# STM32.net
KiCad netlist of a schematic drawn in Altium Designer
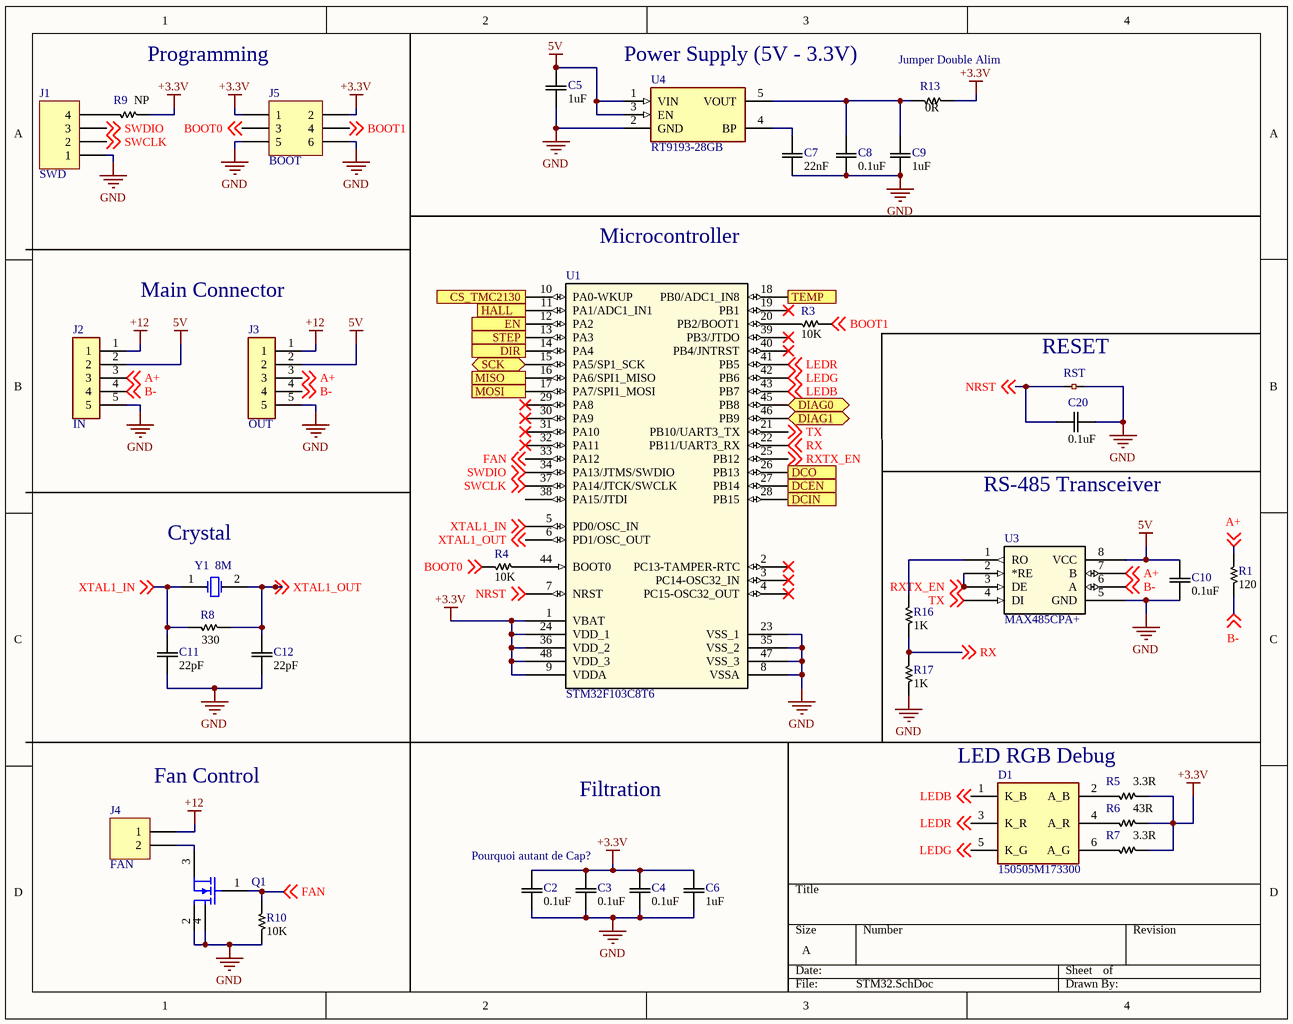
[diagram p0: STM32.SchDoc]

(export (version "E")
  (design (tool "Eeschema 10.0.6"))
  (components
    (comp (ref "C2")
      (value "0.1uF")
      (footprint "0603")
      (description "Capacitor SMD 1206")
      (fields
        (field (name "MANUFACTURER_PART_NUMBER") "12065A820JAT2A")
        (field (name "Comment") "Capacitor 1206")
        (field (name "COPYRIGHT") "Copyright (C) 2018 Accelerated Designs. All rights reserved")
      )
      (libsource (lib "Schematic_Emile") (part "Capacitor 1206"))
    )
    (comp (ref "C3")
      (value "0.1uF")
      (footprint "0603")
      (description "Capacitor SMD 1206")
      (fields
        (field (name "MANUFACTURER_PART_NUMBER") "12065A820JAT2A")
        (field (name "Comment") "Capacitor 1206")
        (field (name "COPYRIGHT") "Copyright (C) 2018 Accelerated Designs. All rights reserved")
      )
      (libsource (lib "Schematic_Emile") (part "Capacitor 1206"))
    )
    (comp (ref "C4")
      (value "0.1uF")
      (footprint "0603")
      (description "Capacitor SMD 1206")
      (fields
        (field (name "MANUFACTURER_PART_NUMBER") "12065A820JAT2A")
        (field (name "Comment") "Capacitor 1206")
        (field (name "COPYRIGHT") "Copyright (C) 2018 Accelerated Designs. All rights reserved")
      )
      (libsource (lib "Schematic_Emile") (part "Capacitor 1206"))
    )
    (comp (ref "C5")
      (value "1uF")
      (footprint "0603")
      (description "Capacitor SMD 1206")
      (fields
        (field (name "MANUFACTURER_PART_NUMBER") "12065A820JAT2A")
        (field (name "Comment") "Capacitor 1206")
        (field (name "COPYRIGHT") "Copyright (C) 2018 Accelerated Designs. All rights reserved")
      )
      (libsource (lib "Schematic_Emile") (part "Capacitor 1206"))
    )
    (comp (ref "C6")
      (value "1uF")
      (footprint "0603")
      (description "Capacitor SMD 1206")
      (fields
        (field (name "MANUFACTURER_PART_NUMBER") "12065A820JAT2A")
        (field (name "Comment") "Capacitor 1206")
        (field (name "COPYRIGHT") "Copyright (C) 2018 Accelerated Designs. All rights reserved")
      )
      (libsource (lib "Schematic_Emile") (part "Capacitor 1206"))
    )
    (comp (ref "C7")
      (value "22nF")
      (footprint "0603")
      (description "Capacitor SMD 1206")
      (fields
        (field (name "MANUFACTURER_PART_NUMBER") "12065A820JAT2A")
        (field (name "Comment") "Capacitor 1206")
        (field (name "COPYRIGHT") "Copyright (C) 2018 Accelerated Designs. All rights reserved")
      )
      (libsource (lib "Schematic_Emile") (part "Capacitor 1206"))
    )
    (comp (ref "C8")
      (value "0.1uF")
      (footprint "0603")
      (description "Capacitor SMD 1206")
      (fields
        (field (name "MANUFACTURER_PART_NUMBER") "12065A820JAT2A")
        (field (name "Comment") "Capacitor 1206")
        (field (name "COPYRIGHT") "Copyright (C) 2018 Accelerated Designs. All rights reserved")
      )
      (libsource (lib "Schematic_Emile") (part "Capacitor 1206"))
    )
    (comp (ref "C9")
      (value "1uF")
      (footprint "0603")
      (description "Capacitor SMD 1206")
      (fields
        (field (name "MANUFACTURER_PART_NUMBER") "12065A820JAT2A")
        (field (name "Comment") "Capacitor 1206")
        (field (name "COPYRIGHT") "Copyright (C) 2018 Accelerated Designs. All rights reserved")
      )
      (libsource (lib "Schematic_Emile") (part "Capacitor 1206"))
    )
    (comp (ref "C10")
      (value "0.1uF")
      (footprint "0603")
      (description "Capacitor SMD 1206")
      (fields
        (field (name "MANUFACTURER_PART_NUMBER") "12065A820JAT2A")
        (field (name "Comment") "Capacitor 1206")
        (field (name "COPYRIGHT") "Copyright (C) 2018 Accelerated Designs. All rights reserved")
      )
      (libsource (lib "Schematic_Emile") (part "Capacitor 1206"))
    )
    (comp (ref "C11")
      (value "22pF")
      (footprint "0603")
      (description "Capacitor SMD 1206")
      (fields
        (field (name "MANUFACTURER_PART_NUMBER") "12065A820JAT2A")
        (field (name "Comment") "Capacitor 1206")
        (field (name "COPYRIGHT") "Copyright (C) 2018 Accelerated Designs. All rights reserved")
      )
      (libsource (lib "Schematic_Emile") (part "Capacitor 1206"))
    )
    (comp (ref "C12")
      (value "22pF")
      (footprint "0603")
      (description "Capacitor SMD 1206")
      (fields
        (field (name "MANUFACTURER_PART_NUMBER") "12065A820JAT2A")
        (field (name "Comment") "Capacitor 1206")
        (field (name "COPYRIGHT") "Copyright (C) 2018 Accelerated Designs. All rights reserved")
      )
      (libsource (lib "Schematic_Emile") (part "Capacitor 1206"))
    )
    (comp (ref "C20")
      (value "0.1uF")
      (footprint "0603")
      (description "Capacitor SMD 1206")
      (fields
        (field (name "MANUFACTURER_PART_NUMBER") "12065A820JAT2A")
        (field (name "Comment") "Capacitor 1206")
        (field (name "COPYRIGHT") "Copyright (C) 2018 Accelerated Designs. All rights reserved")
      )
      (libsource (lib "Schematic_Emile") (part "Capacitor 1206"))
    )
    (comp (ref "D1")
      (value "150505M173300")
      (footprint "LED 5050")
      (description "LED")
      (fields
        (field (name "MOUSER PART NUMBER") "710-150505M173300")
        (field (name "RS PART NUMBER") "1766248P")
      )
      (libsource (lib "Schematic_Emile") (part "150505M173300"))
    )
    (comp (ref "J1")
      (value "SWD")
      (footprint "HDR1X4")
      (description "Header, 4-Pin")
      (fields (field (name "PUBLISHER") "Altium Limited"))
      (libsource (lib "Miscellaneous Connectors") (part "Header 4"))
    )
    (comp (ref "J2")
      (value "IN")
      (footprint "JST 5POS 2.5mm 90°")
      (description "Connector")
      (fields (field (name "MANUFACTURER_PART_NUMBER") "S5B-XH-A-1(LF)(SN)"))
      (libsource (lib "Schematic_Emile") (part "JST 5POS"))
    )
    (comp (ref "J3")
      (value "OUT")
      (footprint "JST 5POS 2.5mm 90°")
      (description "Connector")
      (fields (field (name "MANUFACTURER_PART_NUMBER") "S5B-XH-A-1(LF)(SN)"))
      (libsource (lib "Schematic_Emile") (part "JST 5POS"))
    )
    (comp (ref "J4")
      (value "FAN")
      (footprint "HDR1X2")
      (description "Header, 2-Pin")
      (fields (field (name "PUBLISHER") "Altium Limited"))
      (libsource (lib "Miscellaneous Connectors") (part "Header 2"))
    )
    (comp (ref "J5")
      (value "BOOT")
      (footprint "Header 3x2 1.27mm SMD")
      (description "Header, 3-Pin, Dual row")
      (fields (field (name "PUBLISHER") "Altium Limited"))
      (libsource (lib "Miscellaneous Connectors") (part "Header 3X2"))
    )
    (comp (ref "Q1")
      (value "MOSFET N-CH")
      (footprint "SOT223_M")
      (description "55V 7A SOT223")
      (libsource (lib "Schematic_Emile") (part "MOSFET N-CH"))
    )
    (comp (ref "R1")
      (value "120")
      (footprint "0603")
      (description "Resistor 0603 SMD")
      (fields
        (field (name "MANUFACTURER_PART_NUMBER") "ERJ8CWFR024V")
        (field (name "Comment") "Resistor 0603")
        (field (name "COPYRIGHT") "Copyright (C) 2018 Accelerated Designs. All rights reserved")
      )
      (libsource (lib "Schematic_Emile") (part "Resistor 1206"))
    )
    (comp (ref "R3")
      (value "10K")
      (footprint "0603")
      (description "Resistor 1206 SMD")
      (fields
        (field (name "MANUFACTURER_PART_NUMBER") "ERJ8CWFR024V")
        (field (name "Comment") "Resistor 1206")
        (field (name "COPYRIGHT") "Copyright (C) 2018 Accelerated Designs. All rights reserved")
      )
      (libsource (lib "Schematic_Emile") (part "Resistor 1206"))
    )
    (comp (ref "R4")
      (value "10K")
      (footprint "0603")
      (description "Resistor 1206 SMD")
      (fields
        (field (name "MANUFACTURER_PART_NUMBER") "ERJ8CWFR024V")
        (field (name "Comment") "Resistor 1206")
        (field (name "COPYRIGHT") "Copyright (C) 2018 Accelerated Designs. All rights reserved")
      )
      (libsource (lib "Schematic_Emile") (part "Resistor 1206"))
    )
    (comp (ref "R5")
      (value "3.3R")
      (footprint "0603")
      (description "Resistor 0603 SMD")
      (fields
        (field (name "MANUFACTURER_PART_NUMBER") "ERJ8CWFR024V")
        (field (name "Comment") "Resistor 0603")
        (field (name "COPYRIGHT") "Copyright (C) 2018 Accelerated Designs. All rights reserved")
      )
      (libsource (lib "Schematic_Emile") (part "Resistor 1206"))
    )
    (comp (ref "R6")
      (value "43R")
      (footprint "0603")
      (description "Resistor 0603 SMD")
      (fields
        (field (name "MANUFACTURER_PART_NUMBER") "ERJ8CWFR024V")
        (field (name "Comment") "Resistor 0603")
        (field (name "COPYRIGHT") "Copyright (C) 2018 Accelerated Designs. All rights reserved")
      )
      (libsource (lib "Schematic_Emile") (part "Resistor 1206"))
    )
    (comp (ref "R7")
      (value "3.3R")
      (footprint "0603")
      (description "Resistor 0603 SMD")
      (fields
        (field (name "MANUFACTURER_PART_NUMBER") "ERJ8CWFR024V")
        (field (name "Comment") "Resistor 0603")
        (field (name "COPYRIGHT") "Copyright (C) 2018 Accelerated Designs. All rights reserved")
      )
      (libsource (lib "Schematic_Emile") (part "Resistor 1206"))
    )
    (comp (ref "R8")
      (value "330")
      (footprint "0603")
      (description "Resistor 0603 SMD")
      (fields
        (field (name "MANUFACTURER_PART_NUMBER") "ERJ8CWFR024V")
        (field (name "Comment") "Resistor 0603")
        (field (name "COPYRIGHT") "Copyright (C) 2018 Accelerated Designs. All rights reserved")
      )
      (libsource (lib "Schematic_Emile") (part "Resistor 1206"))
    )
    (comp (ref "R9")
      (value "NP")
      (footprint "0603")
      (description "Resistor 1206 SMD")
      (fields
        (field (name "MANUFACTURER_PART_NUMBER") "ERJ8CWFR024V")
        (field (name "Comment") "Jumper 0603")
        (field (name "COPYRIGHT") "Copyright (C) 2018 Accelerated Designs. All rights reserved")
      )
      (libsource (lib "Schematic_Emile") (part "Resistor 1206"))
    )
    (comp (ref "R10")
      (value "10K")
      (footprint "0603")
      (description "Resistor 0603 SMD")
      (fields
        (field (name "MANUFACTURER_PART_NUMBER") "ERJ8CWFR024V")
        (field (name "Comment") "Resistor 0603")
        (field (name "COPYRIGHT") "Copyright (C) 2018 Accelerated Designs. All rights reserved")
      )
      (libsource (lib "Schematic_Emile") (part "Resistor 1206"))
    )
    (comp (ref "R13")
      (value "0R")
      (footprint "0603")
      (description "Resistor 1206 SMD")
      (fields
        (field (name "MANUFACTURER_PART_NUMBER") "ERJ8CWFR024V")
        (field (name "Comment") "Jumper 0603")
        (field (name "COPYRIGHT") "Copyright (C) 2018 Accelerated Designs. All rights reserved")
      )
      (libsource (lib "Schematic_Emile") (part "Resistor 1206"))
    )
    (comp (ref "R16")
      (value "1K")
      (footprint "0603")
      (description "Resistor 0603 SMD")
      (fields
        (field (name "MANUFACTURER_PART_NUMBER") "ERJ8CWFR024V")
        (field (name "Comment") "Resistor 0603")
        (field (name "COPYRIGHT") "Copyright (C) 2018 Accelerated Designs. All rights reserved")
      )
      (libsource (lib "Schematic_Emile") (part "Resistor 1206"))
    )
    (comp (ref "R17")
      (value "1K")
      (footprint "0603")
      (description "Resistor 0603 SMD")
      (fields
        (field (name "MANUFACTURER_PART_NUMBER") "ERJ8CWFR024V")
        (field (name "Comment") "Resistor 0603")
        (field (name "COPYRIGHT") "Copyright (C) 2018 Accelerated Designs. All rights reserved")
      )
      (libsource (lib "Schematic_Emile") (part "Resistor 1206"))
    )
    (comp (ref "RST")
      (value "PAD")
      (footprint "PAD")
      (description "SMD Pad for contact")
      (libsource (lib "Schematic_Emile") (part "PAD"))
    )
    (comp (ref "U1")
      (value "STM32F103C8T6")
      (footprint "LQFP-48")
      (description "Integrated Circuit STM32")
      (fields (field (name "COPYRIGHT") "Copyright (C) 2018 Accelerated Designs. All rights reserved"))
      (libsource (lib "Schematic_Emile") (part "STM32F103C8T6"))
    )
    (comp (ref "U3")
      (value "MAX485CPA+")
      (footprint "DIP 8 - 3D")
      (description "RS485 Communication")
      (fields (field (name "COPYRIGHT") "Copyright (C) 2018 Accelerated Designs. All rights reserved"))
      (libsource (lib "Schematic_Emile") (part "MAX485CPA+"))
    )
    (comp (ref "U4")
      (value "RT9193-28GB")
      (footprint "SamacSys:SOT94P279X130-5N")
      (description "Voltage Regulator 3.3V")
      (libsource (lib "Schematic_Emile") (part "RT9193-28GB"))
    )
    (comp (ref "Y1")
      (value "8M")
      (footprint "ATS080B-E")
      (description "Crystal Oscillator")
      (fields (field (name "PUBLISHER") "Altium Limited"))
      (libsource (lib "Miscellaneous Devices") (part "XTAL"))
    )
  )
  (nets
    (net (code "1") (name "+3.3V") (class "Default")
      (node (ref "C2") (pin "2") (pinfunction "2_2") (pintype "passive"))
      (node (ref "C3") (pin "2") (pinfunction "2_2") (pintype "passive"))
      (node (ref "C4") (pin "2") (pinfunction "2_2") (pintype "passive"))
      (node (ref "C6") (pin "2") (pinfunction "2_2") (pintype "passive"))
      (node (ref "J5") (pin "1") (pinfunction "1_1") (pintype "passive"))
      (node (ref "J5") (pin "2") (pinfunction "2_2") (pintype "passive"))
      (node (ref "R13") (pin "2") (pinfunction "2_2") (pintype "passive"))
      (node (ref "R5") (pin "2") (pinfunction "2_2") (pintype "passive"))
      (node (ref "R6") (pin "2") (pinfunction "2_2") (pintype "passive"))
      (node (ref "R7") (pin "2") (pinfunction "2_2") (pintype "passive"))
      (node (ref "R9") (pin "2") (pinfunction "2_2") (pintype "passive"))
      (node (ref "U1") (pin "1") (pinfunction "VBAT_1") (pintype "power_in"))
      (node (ref "U1") (pin "24") (pinfunction "VDD_1_24") (pintype "power_in"))
      (node (ref "U1") (pin "36") (pinfunction "VDD_2_36") (pintype "power_in"))
      (node (ref "U1") (pin "48") (pinfunction "VDD_3_48") (pintype "power_in"))
      (node (ref "U1") (pin "9") (pinfunction "VDDA_9") (pintype "power_in"))
    )
    (net (code "2") (name "+12") (class "Default")
      (node (ref "J2") (pin "1") (pinfunction "1_1") (pintype "passive"))
      (node (ref "J3") (pin "1") (pinfunction "1_1") (pintype "passive"))
      (node (ref "J4") (pin "1") (pinfunction "1_1") (pintype "passive"))
    )
    (net (code "3") (name "/CS_TMC2130") (class "Default")
      (node (ref "U1") (pin "10") (pinfunction "PA0-WKUP_10") (pintype "bidirectional"))
    )
    (net (code "4") (name "/DCEN") (class "Default")
      (node (ref "U1") (pin "27") (pinfunction "PB14_27") (pintype "bidirectional"))
    )
    (net (code "5") (name "/DCIN") (class "Default")
      (node (ref "U1") (pin "28") (pinfunction "PB15_28") (pintype "bidirectional"))
    )
    (net (code "6") (name "/DCO") (class "Default")
      (node (ref "U1") (pin "26") (pinfunction "PB13_26") (pintype "bidirectional"))
    )
    (net (code "7") (name "/DIAG0") (class "Default")
      (node (ref "U1") (pin "45") (pinfunction "PB8_45") (pintype "bidirectional"))
    )
    (net (code "8") (name "/DIAG1") (class "Default")
      (node (ref "U1") (pin "46") (pinfunction "PB9_46") (pintype "bidirectional"))
    )
    (net (code "9") (name "/DIR") (class "Default")
      (node (ref "U1") (pin "14") (pinfunction "PA4_14") (pintype "bidirectional"))
    )
    (net (code "10") (name "/EN") (class "Default")
      (node (ref "U1") (pin "12") (pinfunction "PA2_12") (pintype "bidirectional"))
    )
    (net (code "11") (name "/HALL") (class "Default")
      (node (ref "U1") (pin "11") (pinfunction "PA1/ADC1_IN1_11") (pintype "bidirectional"))
    )
    (net (code "12") (name "/MISO") (class "Default")
      (node (ref "U1") (pin "16") (pinfunction "PA6/SPI1_MISO_16") (pintype "bidirectional"))
    )
    (net (code "13") (name "/MOSI") (class "Default")
      (node (ref "U1") (pin "17") (pinfunction "PA7/SPI1_MOSI_17") (pintype "bidirectional"))
    )
    (net (code "14") (name "/SCK") (class "Default")
      (node (ref "U1") (pin "15") (pinfunction "PA5/SP1_SCK_15") (pintype "bidirectional"))
    )
    (net (code "15") (name "/STEP") (class "Default")
      (node (ref "U1") (pin "13") (pinfunction "PA3_13") (pintype "bidirectional"))
    )
    (net (code "16") (name "/TEMP") (class "Default")
      (node (ref "U1") (pin "18") (pinfunction "PB0/ADC1_IN8_18") (pintype "bidirectional"))
    )
    (net (code "17") (name "5V") (class "Default")
      (node (ref "C10") (pin "2") (pinfunction "2_2") (pintype "passive"))
      (node (ref "C5") (pin "2") (pinfunction "2_2") (pintype "passive"))
      (node (ref "J2") (pin "2") (pinfunction "2_2") (pintype "passive"))
      (node (ref "J3") (pin "2") (pinfunction "2_2") (pintype "passive"))
      (node (ref "U3") (pin "8") (pinfunction "VCC_8") (pintype "power_in"))
      (node (ref "U4") (pin "1") (pinfunction "VIN_1") (pintype "input"))
      (node (ref "U4") (pin "3") (pinfunction "EN_3") (pintype "input"))
    )
    (net (code "18") (name "A+") (class "Default")
      (node (ref "J2") (pin "3") (pinfunction "3_3") (pintype "passive"))
      (node (ref "J3") (pin "3") (pinfunction "3_3") (pintype "passive"))
      (node (ref "R1") (pin "2") (pinfunction "2_2") (pintype "passive"))
      (node (ref "U3") (pin "7") (pinfunction "B_7") (pintype "bidirectional"))
    )
    (net (code "19") (name "B-") (class "Default")
      (node (ref "J2") (pin "4") (pinfunction "4_4") (pintype "passive"))
      (node (ref "J3") (pin "4") (pinfunction "4_4") (pintype "passive"))
      (node (ref "R1") (pin "1") (pinfunction "1_1") (pintype "passive"))
      (node (ref "U3") (pin "6") (pinfunction "A_6") (pintype "bidirectional"))
    )
    (net (code "20") (name "BOOT0") (class "Default")
      (node (ref "J5") (pin "3") (pinfunction "3_3") (pintype "passive"))
      (node (ref "R4") (pin "1") (pinfunction "1_1") (pintype "passive"))
    )
    (net (code "21") (name "BOOT1") (class "Default")
      (node (ref "J5") (pin "4") (pinfunction "4_4") (pintype "passive"))
      (node (ref "R3") (pin "2") (pinfunction "2_2") (pintype "passive"))
    )
    (net (code "22") (name "FAN") (class "Default")
      (node (ref "Q1") (pin "1") (pinfunction "G_1") (pintype "passive"))
      (node (ref "R10") (pin "2") (pinfunction "2_2") (pintype "passive"))
      (node (ref "U1") (pin "33") (pinfunction "PA12_33") (pintype "bidirectional"))
    )
    (net (code "23") (name "GND") (class "Default")
      (node (ref "C10") (pin "1") (pinfunction "1_1") (pintype "passive"))
      (node (ref "C11") (pin "1") (pinfunction "1_1") (pintype "passive"))
      (node (ref "C12") (pin "1") (pinfunction "1_1") (pintype "passive"))
      (node (ref "C2") (pin "1") (pinfunction "1_1") (pintype "passive"))
      (node (ref "C20") (pin "1") (pinfunction "1_1") (pintype "passive"))
      (node (ref "C3") (pin "1") (pinfunction "1_1") (pintype "passive"))
      (node (ref "C4") (pin "1") (pinfunction "1_1") (pintype "passive"))
      (node (ref "C5") (pin "1") (pinfunction "1_1") (pintype "passive"))
      (node (ref "C6") (pin "1") (pinfunction "1_1") (pintype "passive"))
      (node (ref "C7") (pin "1") (pinfunction "1_1") (pintype "passive"))
      (node (ref "C8") (pin "1") (pinfunction "1_1") (pintype "passive"))
      (node (ref "C9") (pin "1") (pinfunction "1_1") (pintype "passive"))
      (node (ref "J1") (pin "1") (pinfunction "1_1") (pintype "passive"))
      (node (ref "J2") (pin "5") (pinfunction "5_5") (pintype "passive"))
      (node (ref "J3") (pin "5") (pinfunction "5_5") (pintype "passive"))
      (node (ref "J5") (pin "5") (pinfunction "5_5") (pintype "passive"))
      (node (ref "J5") (pin "6") (pinfunction "6_6") (pintype "passive"))
      (node (ref "Q1") (pin "2") (pinfunction "D_2") (pintype "passive"))
      (node (ref "Q1") (pin "4") (pinfunction "D_4") (pintype "passive"))
      (node (ref "R10") (pin "1") (pinfunction "1_1") (pintype "passive"))
      (node (ref "R17") (pin "2") (pinfunction "2_2") (pintype "passive"))
      (node (ref "RST") (pin "1") (pinfunction "1_1") (pintype "passive"))
      (node (ref "U1") (pin "23") (pinfunction "VSS_1_23") (pintype "power_in"))
      (node (ref "U1") (pin "35") (pinfunction "VSS_2_35") (pintype "power_in"))
      (node (ref "U1") (pin "47") (pinfunction "VSS_3_47") (pintype "power_in"))
      (node (ref "U1") (pin "8") (pinfunction "VSSA_8") (pintype "power_in"))
      (node (ref "U3") (pin "5") (pinfunction "GND_5") (pintype "power_in"))
      (node (ref "U4") (pin "2") (pinfunction "GND_2") (pintype "power_in"))
    )
    (net (code "24") (name "LEDB") (class "Default")
      (node (ref "D1") (pin "1") (pinfunction "K_B_1") (pintype "passive"))
      (node (ref "U1") (pin "43") (pinfunction "PB7_43") (pintype "bidirectional"))
    )
    (net (code "25") (name "LEDG") (class "Default")
      (node (ref "D1") (pin "5") (pinfunction "K_G_5") (pintype "passive"))
      (node (ref "U1") (pin "42") (pinfunction "PB6_42") (pintype "bidirectional"))
    )
    (net (code "26") (name "LEDR") (class "Default")
      (node (ref "D1") (pin "3") (pinfunction "K_R_3") (pintype "passive"))
      (node (ref "U1") (pin "41") (pinfunction "PB5_41") (pintype "bidirectional"))
    )
    (net (code "27") (name "NRST") (class "Default")
      (node (ref "C20") (pin "2") (pinfunction "2_2") (pintype "passive"))
      (node (ref "RST") (pin "2") (pinfunction "2_2") (pintype "passive"))
      (node (ref "U1") (pin "7") (pinfunction "NRST_7") (pintype "bidirectional"))
    )
    (net (code "28") (name "Net-(D1-A_B)") (class "Default")
      (node (ref "D1") (pin "2") (pinfunction "A_B_2") (pintype "passive"))
      (node (ref "R5") (pin "1") (pinfunction "1_1") (pintype "passive"))
    )
    (net (code "29") (name "Net-(D1-A_G)") (class "Default")
      (node (ref "D1") (pin "6") (pinfunction "A_G_6") (pintype "passive"))
      (node (ref "R7") (pin "1") (pinfunction "1_1") (pintype "passive"))
    )
    (net (code "30") (name "Net-(D1-A_R)") (class "Default")
      (node (ref "D1") (pin "4") (pinfunction "A_R_4") (pintype "passive"))
      (node (ref "R6") (pin "1") (pinfunction "1_1") (pintype "passive"))
    )
    (net (code "31") (name "Net-(J1-Pad4)") (class "Default")
      (node (ref "J1") (pin "4") (pinfunction "4_4") (pintype "passive"))
      (node (ref "R9") (pin "1") (pinfunction "1_1") (pintype "passive"))
    )
    (net (code "32") (name "Net-(Q1-S)") (class "Default")
      (node (ref "J4") (pin "2") (pinfunction "2_2") (pintype "passive"))
      (node (ref "Q1") (pin "3") (pinfunction "S_3") (pintype "passive"))
    )
    (net (code "33") (name "Net-(U1-BOOT0)") (class "Default")
      (node (ref "R4") (pin "2") (pinfunction "2_2") (pintype "passive"))
      (node (ref "U1") (pin "44") (pinfunction "BOOT0_44") (pintype "input"))
    )
    (net (code "34") (name "Net-(U1-PB2{slash}BOOT1)") (class "Default")
      (node (ref "R3") (pin "1") (pinfunction "1_1") (pintype "passive"))
      (node (ref "U1") (pin "20") (pinfunction "PB2/BOOT1_20") (pintype "bidirectional"))
    )
    (net (code "35") (name "Net-(U3-RO)") (class "Default")
      (node (ref "R16") (pin "1") (pinfunction "1_1") (pintype "passive"))
      (node (ref "U3") (pin "1") (pinfunction "RO_1") (pintype "output"))
    )
    (net (code "36") (name "Net-(U4-BP)") (class "Default")
      (node (ref "C7") (pin "2") (pinfunction "2_2") (pintype "passive"))
      (node (ref "U4") (pin "4") (pinfunction "BP_4") (pintype "passive"))
    )
    (net (code "37") (name "Net-(U4-VOUT)") (class "Default")
      (node (ref "C8") (pin "2") (pinfunction "2_2") (pintype "passive"))
      (node (ref "C9") (pin "2") (pinfunction "2_2") (pintype "passive"))
      (node (ref "R13") (pin "1") (pinfunction "1_1") (pintype "passive"))
      (node (ref "U4") (pin "5") (pinfunction "VOUT_5") (pintype "passive"))
    )
    (net (code "38") (name "RX") (class "Default")
      (node (ref "R16") (pin "2") (pinfunction "2_2") (pintype "passive"))
      (node (ref "R17") (pin "1") (pinfunction "1_1") (pintype "passive"))
      (node (ref "U1") (pin "22") (pinfunction "PB11/UART3_RX_22") (pintype "bidirectional"))
    )
    (net (code "39") (name "RXTX_EN") (class "Default")
      (node (ref "U1") (pin "25") (pinfunction "PB12_25") (pintype "bidirectional"))
      (node (ref "U3") (pin "2") (pinfunction "*RE_2") (pintype "input"))
      (node (ref "U3") (pin "3") (pinfunction "DE_3") (pintype "input"))
    )
    (net (code "40") (name "SWCLK") (class "Default")
      (node (ref "J1") (pin "2") (pinfunction "2_2") (pintype "passive"))
      (node (ref "U1") (pin "37") (pinfunction "PA14/JTCK/SWCLK_37") (pintype "bidirectional"))
    )
    (net (code "41") (name "SWDIO") (class "Default")
      (node (ref "J1") (pin "3") (pinfunction "3_3") (pintype "passive"))
      (node (ref "U1") (pin "34") (pinfunction "PA13/JTMS/SWDIO_34") (pintype "bidirectional"))
    )
    (net (code "42") (name "TX") (class "Default")
      (node (ref "U1") (pin "21") (pinfunction "PB10/UART3_TX_21") (pintype "bidirectional"))
      (node (ref "U3") (pin "4") (pinfunction "DI_4") (pintype "input"))
    )
    (net (code "43") (name "XTAL1_IN") (class "Default")
      (node (ref "C11") (pin "2") (pinfunction "2_2") (pintype "passive"))
      (node (ref "R8") (pin "1") (pinfunction "1_1") (pintype "passive"))
      (node (ref "U1") (pin "5") (pinfunction "PD0/OSC_IN_5") (pintype "bidirectional"))
      (node (ref "Y1") (pin "1") (pinfunction "OSC1_1") (pintype "passive"))
    )
    (net (code "44") (name "XTAL1_OUT") (class "Default")
      (node (ref "C12") (pin "2") (pinfunction "2_2") (pintype "passive"))
      (node (ref "R8") (pin "2") (pinfunction "2_2") (pintype "passive"))
      (node (ref "U1") (pin "6") (pinfunction "PD1/OSC_OUT_6") (pintype "bidirectional"))
      (node (ref "Y1") (pin "2") (pinfunction "OSC2_2") (pintype "passive"))
    )
    (net (code "45") (name "unconnected-(U1-PA8-Pad29)") (class "Default")
      (node (ref "U1") (pin "29") (pinfunction "PA8_29") (pintype "bidirectional+no_connect"))
    )
    (net (code "46") (name "unconnected-(U1-PA9-Pad30)") (class "Default")
      (node (ref "U1") (pin "30") (pinfunction "PA9_30") (pintype "bidirectional+no_connect"))
    )
    (net (code "47") (name "unconnected-(U1-PA10-Pad31)") (class "Default")
      (node (ref "U1") (pin "31") (pinfunction "PA10_31") (pintype "bidirectional+no_connect"))
    )
    (net (code "48") (name "unconnected-(U1-PA11-Pad32)") (class "Default")
      (node (ref "U1") (pin "32") (pinfunction "PA11_32") (pintype "bidirectional+no_connect"))
    )
    (net (code "49") (name "unconnected-(U1-PA15{slash}JTDI-Pad38)") (class "Default")
      (node (ref "U1") (pin "38") (pinfunction "PA15/JTDI_38") (pintype "bidirectional"))
    )
    (net (code "50") (name "unconnected-(U1-PB1-Pad19)") (class "Default")
      (node (ref "U1") (pin "19") (pinfunction "PB1_19") (pintype "bidirectional+no_connect"))
    )
    (net (code "51") (name "unconnected-(U1-PB3{slash}JTDO-Pad39)") (class "Default")
      (node (ref "U1") (pin "39") (pinfunction "PB3/JTDO_39") (pintype "bidirectional+no_connect"))
    )
    (net (code "52") (name "unconnected-(U1-PB4{slash}JNTRST-Pad40)") (class "Default")
      (node (ref "U1") (pin "40") (pinfunction "PB4/JNTRST_40") (pintype "bidirectional+no_connect"))
    )
    (net (code "53") (name "unconnected-(U1-PC13-TAMPER-RTC-Pad2)") (class "Default")
      (node (ref "U1") (pin "2") (pinfunction "PC13-TAMPER-RTC_2") (pintype "bidirectional+no_connect"))
    )
    (net (code "54") (name "unconnected-(U1-PC14-OSC32_IN-Pad3)") (class "Default")
      (node (ref "U1") (pin "3") (pinfunction "PC14-OSC32_IN_3") (pintype "bidirectional+no_connect"))
    )
    (net (code "55") (name "unconnected-(U1-PC15-OSC32_OUT-Pad4)") (class "Default")
      (node (ref "U1") (pin "4") (pinfunction "PC15-OSC32_OUT_4") (pintype "bidirectional+no_connect"))
    )
  )
)
